# DAC_IO.net
KiCad netlist of a schematic drawn in Altium Designer
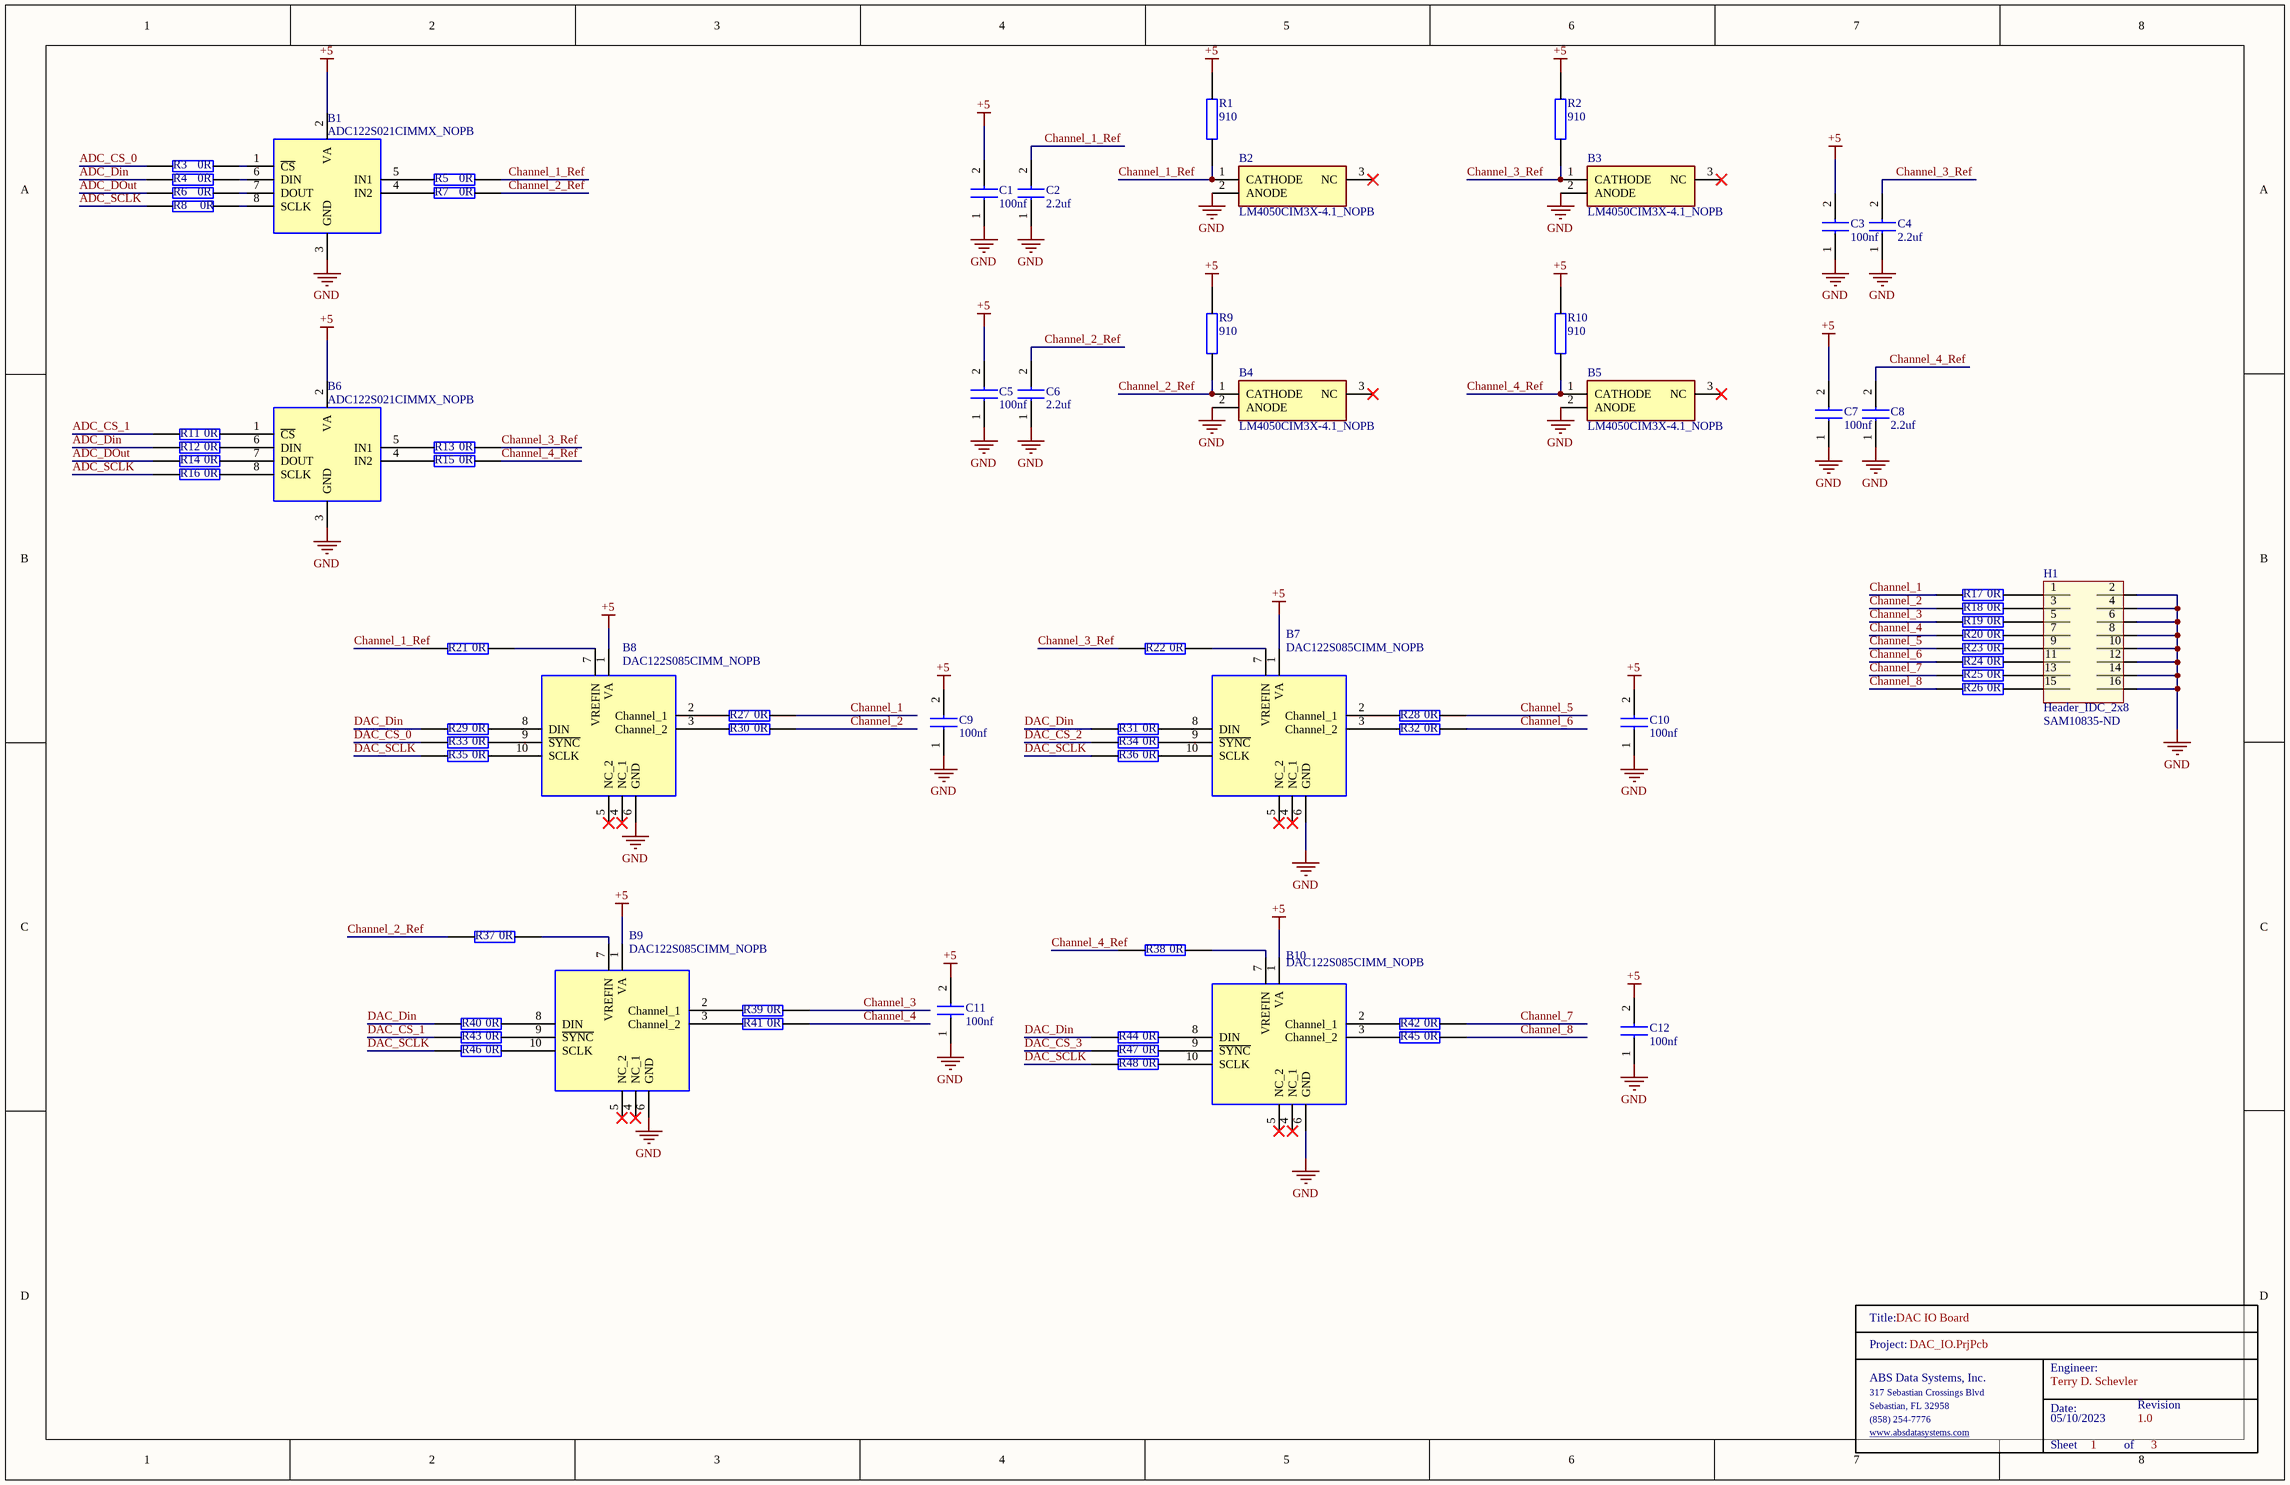
[diagram p0: DAC_IO.SchDoc]

(export (version "E")
  (design (tool "Eeschema 10.0.6"))
  (components
    (comp (ref "B1")
      (value "ADC122S021CIMMX_NOPB")
      (footprint "SOP65P490X110-8N")
      (description "2 Channel, 50 ksps to 200 ksps 12-Bit A/D Converter")
      (fields
        (field (name "MOUSER PART NUMBER") "926-A122S021CIMMXNPB")
        (field (name "MANUFACTURER_PART_NUMBER") "ADC122S021CIMMX/NOPB")
      )
      (libsource (lib "SemiConductors") (part "ADC122S021CIMMX_NOPB"))
    )
    (comp (ref "B2")
      (value "LM4050CIM3X-4.1_NOPB")
      (footprint "SOT95P237X95-3N")
      (description "50ppm/C Precision Micropower Shunt Voltage Reference")
      (fields
        (field (name "MOUSER PART NUMBER") "926-LM4050CIM3X41NPB")
        (field (name "MANUFACTURER_PART_NUMBER") "LM4050CIM3X-4.1/NOPB")
      )
      (libsource (lib "SemiConductors") (part "LM4050CIM3X-4.1_NOPB"))
    )
    (comp (ref "B3")
      (value "LM4050CIM3X-4.1_NOPB")
      (footprint "SOT95P237X95-3N")
      (description "50ppm/C Precision Micropower Shunt Voltage Reference")
      (fields
        (field (name "MOUSER PART NUMBER") "926-LM4050CIM3X41NPB")
        (field (name "MANUFACTURER_PART_NUMBER") "LM4050CIM3X-4.1/NOPB")
      )
      (libsource (lib "SemiConductors") (part "LM4050CIM3X-4.1_NOPB"))
    )
    (comp (ref "B4")
      (value "LM4050CIM3X-4.1_NOPB")
      (footprint "SOT95P237X95-3N")
      (description "50ppm/C Precision Micropower Shunt Voltage Reference")
      (fields
        (field (name "MOUSER PART NUMBER") "926-LM4050CIM3X41NPB")
        (field (name "MANUFACTURER_PART_NUMBER") "LM4050CIM3X-4.1/NOPB")
      )
      (libsource (lib "SemiConductors") (part "LM4050CIM3X-4.1_NOPB"))
    )
    (comp (ref "B5")
      (value "LM4050CIM3X-4.1_NOPB")
      (footprint "SOT95P237X95-3N")
      (description "50ppm/C Precision Micropower Shunt Voltage Reference")
      (fields
        (field (name "MOUSER PART NUMBER") "926-LM4050CIM3X41NPB")
        (field (name "MANUFACTURER_PART_NUMBER") "LM4050CIM3X-4.1/NOPB")
      )
      (libsource (lib "SemiConductors") (part "LM4050CIM3X-4.1_NOPB"))
    )
    (comp (ref "B6")
      (value "ADC122S021CIMMX_NOPB")
      (footprint "SOP65P490X110-8N")
      (description "2 Channel, 50 ksps to 200 ksps 12-Bit A/D Converter")
      (fields
        (field (name "MOUSER PART NUMBER") "926-A122S021CIMMXNPB")
        (field (name "MANUFACTURER_PART_NUMBER") "ADC122S021CIMMX/NOPB")
      )
      (libsource (lib "SemiConductors") (part "ADC122S021CIMMX_NOPB"))
    )
    (comp (ref "B7")
      (value "DAC122S085CIMM_NOPB")
      (footprint "SOP50P490X110-10N")
      (description "12-Bit Micro Power DUAL Digital-to-Analog Converter with Rail-to-Rail Output")
      (fields
        (field (name "MOUSER PART NUMBER") "926-DAC122S085CIMMNO")
        (field (name "MANUFACTURER_PART_NUMBER") "DAC122S085CIMM/NOPB")
      )
      (libsource (lib "SemiConductors") (part "DAC122S085CIMM_NOPB"))
    )
    (comp (ref "B8")
      (value "DAC122S085CIMM_NOPB")
      (footprint "SOP50P490X110-10N")
      (description "12-Bit Micro Power DUAL Digital-to-Analog Converter with Rail-to-Rail Output")
      (fields
        (field (name "MOUSER PART NUMBER") "926-DAC122S085CIMMNO")
        (field (name "MANUFACTURER_PART_NUMBER") "DAC122S085CIMM/NOPB")
      )
      (libsource (lib "SemiConductors") (part "DAC122S085CIMM_NOPB"))
    )
    (comp (ref "B9")
      (value "DAC122S085CIMM_NOPB")
      (footprint "SOP50P490X110-10N")
      (description "12-Bit Micro Power DUAL Digital-to-Analog Converter with Rail-to-Rail Output")
      (fields
        (field (name "MOUSER PART NUMBER") "926-DAC122S085CIMMNO")
        (field (name "MANUFACTURER_PART_NUMBER") "DAC122S085CIMM/NOPB")
      )
      (libsource (lib "SemiConductors") (part "DAC122S085CIMM_NOPB"))
    )
    (comp (ref "B10")
      (value "DAC122S085CIMM_NOPB")
      (footprint "SOP50P490X110-10N")
      (description "12-Bit Micro Power DUAL Digital-to-Analog Converter with Rail-to-Rail Output")
      (fields
        (field (name "MOUSER PART NUMBER") "926-DAC122S085CIMMNO")
        (field (name "MANUFACTURER_PART_NUMBER") "DAC122S085CIMM/NOPB")
      )
      (libsource (lib "SemiConductors") (part "DAC122S085CIMM_NOPB"))
    )
    (comp (ref "C1")
      (value "100nf")
      (footprint "0603")
      (description "Samsung Electro-Mechanics 0603 100nf")
      (libsource (lib "Capacitors") (part "CL10B104JB8NNNC"))
    )
    (comp (ref "C2")
      (value "2.2uf")
      (footprint "0603")
      (description "Samsung Electro-Mechanics 0603 2.2uf")
      (libsource (lib "Capacitors") (part "CL10B225KP8NNNC"))
    )
    (comp (ref "C3")
      (value "100nf")
      (footprint "0603")
      (description "Samsung Electro-Mechanics 0603 100nf")
      (libsource (lib "Capacitors") (part "CL10B104JB8NNNC"))
    )
    (comp (ref "C4")
      (value "2.2uf")
      (footprint "0603")
      (description "Samsung Electro-Mechanics 0603 2.2uf")
      (libsource (lib "Capacitors") (part "CL10B225KP8NNNC"))
    )
    (comp (ref "C5")
      (value "100nf")
      (footprint "0603")
      (description "Samsung Electro-Mechanics 0603 100nf")
      (libsource (lib "Capacitors") (part "CL10B104JB8NNNC"))
    )
    (comp (ref "C6")
      (value "2.2uf")
      (footprint "0603")
      (description "Samsung Electro-Mechanics 0603 2.2uf")
      (libsource (lib "Capacitors") (part "CL10B225KP8NNNC"))
    )
    (comp (ref "C7")
      (value "100nf")
      (footprint "0603")
      (description "Samsung Electro-Mechanics 0603 100nf")
      (libsource (lib "Capacitors") (part "CL10B104JB8NNNC"))
    )
    (comp (ref "C8")
      (value "2.2uf")
      (footprint "0603")
      (description "Samsung Electro-Mechanics 0603 2.2uf")
      (libsource (lib "Capacitors") (part "CL10B225KP8NNNC"))
    )
    (comp (ref "C9")
      (value "100nf")
      (footprint "0603")
      (description "Samsung Electro-Mechanics 0603 100nf")
      (libsource (lib "Capacitors") (part "CL10B104JB8NNNC"))
    )
    (comp (ref "C10")
      (value "100nf")
      (footprint "0603")
      (description "Samsung Electro-Mechanics 0603 100nf")
      (libsource (lib "Capacitors") (part "CL10B104JB8NNNC"))
    )
    (comp (ref "C11")
      (value "100nf")
      (footprint "0603")
      (description "Samsung Electro-Mechanics 0603 100nf")
      (libsource (lib "Capacitors") (part "CL10B104JB8NNNC"))
    )
    (comp (ref "C12")
      (value "100nf")
      (footprint "0603")
      (description "Samsung Electro-Mechanics 0603 100nf")
      (libsource (lib "Capacitors") (part "CL10B104JB8NNNC"))
    )
    (comp (ref "H1")
      (value "Header_IDC_2x8")
      (footprint "HEADER16")
      (description "16 Pin 2x8 Through Hold IDC Connector")
      (fields
        (field (name "MANUFACTURER") "Samtec")
        (field (name "MANUFACTURER PART NUMBER") "TST-108-01-G-D")
        (field (name "SUPPLIER PART NUMBER 1") "SAM10835-ND")
      )
      (libsource (lib "Misc") (part "Header_IDC_2x8"))
    )
    (comp (ref "R1")
      (value "910")
      (footprint "0603")
      (description "YAGEO 0603 910 ohm")
      (fields
        (field (name "MOUSER PART NUMBER") "603-RC0603JR-070RL")
        (field (name "MANUFACTURER_PART_NUMBER") "RC0603JR-070RL")
      )
      (libsource (lib "Resistors") (part "RT0603BRC07910RL"))
    )
    (comp (ref "R2")
      (value "910")
      (footprint "0603")
      (description "YAGEO 0603 910 ohm")
      (fields
        (field (name "MOUSER PART NUMBER") "603-RC0603JR-070RL")
        (field (name "MANUFACTURER_PART_NUMBER") "RC0603JR-070RL")
      )
      (libsource (lib "Resistors") (part "RT0603BRC07910RL"))
    )
    (comp (ref "R3")
      (value "0R")
      (footprint "0603")
      (description "YAGEO 0603 0 ohm")
      (fields
        (field (name "MOUSER PART NUMBER") "603-RC0603JR-070RL")
        (field (name "MANUFACTURER_PART_NUMBER") "RC0603JR-070RL")
      )
      (libsource (lib "Resistors") (part "RC0603JR-070RL"))
    )
    (comp (ref "R4")
      (value "0R")
      (footprint "0603")
      (description "YAGEO 0603 0 ohm")
      (fields
        (field (name "MOUSER PART NUMBER") "603-RC0603JR-070RL")
        (field (name "MANUFACTURER_PART_NUMBER") "RC0603JR-070RL")
      )
      (libsource (lib "Resistors") (part "RC0603JR-070RL"))
    )
    (comp (ref "R5")
      (value "0R")
      (footprint "0603")
      (description "YAGEO 0603 0 ohm")
      (fields
        (field (name "MOUSER PART NUMBER") "603-RC0603JR-070RL")
        (field (name "MANUFACTURER_PART_NUMBER") "RC0603JR-070RL")
      )
      (libsource (lib "Resistors") (part "RC0603JR-070RL"))
    )
    (comp (ref "R6")
      (value "0R")
      (footprint "0603")
      (description "YAGEO 0603 0 ohm")
      (fields
        (field (name "MOUSER PART NUMBER") "603-RC0603JR-070RL")
        (field (name "MANUFACTURER_PART_NUMBER") "RC0603JR-070RL")
      )
      (libsource (lib "Resistors") (part "RC0603JR-070RL"))
    )
    (comp (ref "R7")
      (value "0R")
      (footprint "0603")
      (description "YAGEO 0603 0 ohm")
      (fields
        (field (name "MOUSER PART NUMBER") "603-RC0603JR-070RL")
        (field (name "MANUFACTURER_PART_NUMBER") "RC0603JR-070RL")
      )
      (libsource (lib "Resistors") (part "RC0603JR-070RL"))
    )
    (comp (ref "R8")
      (value "0R")
      (footprint "0603")
      (description "YAGEO 0603 0 ohm")
      (fields
        (field (name "MOUSER PART NUMBER") "603-RC0603JR-070RL")
        (field (name "MANUFACTURER_PART_NUMBER") "RC0603JR-070RL")
      )
      (libsource (lib "Resistors") (part "RC0603JR-070RL"))
    )
    (comp (ref "R9")
      (value "910")
      (footprint "0603")
      (description "YAGEO 0603 910 ohm")
      (fields
        (field (name "MOUSER PART NUMBER") "603-RC0603JR-070RL")
        (field (name "MANUFACTURER_PART_NUMBER") "RC0603JR-070RL")
      )
      (libsource (lib "Resistors") (part "RT0603BRC07910RL"))
    )
    (comp (ref "R10")
      (value "910")
      (footprint "0603")
      (description "YAGEO 0603 910 ohm")
      (fields
        (field (name "MOUSER PART NUMBER") "603-RC0603JR-070RL")
        (field (name "MANUFACTURER_PART_NUMBER") "RC0603JR-070RL")
      )
      (libsource (lib "Resistors") (part "RT0603BRC07910RL"))
    )
    (comp (ref "R11")
      (value "0R")
      (footprint "0603")
      (description "YAGEO 0603 0 ohm")
      (fields
        (field (name "MOUSER PART NUMBER") "603-RC0603JR-070RL")
        (field (name "MANUFACTURER_PART_NUMBER") "RC0603JR-070RL")
      )
      (libsource (lib "Resistors") (part "RC0603JR-070RL"))
    )
    (comp (ref "R12")
      (value "0R")
      (footprint "0603")
      (description "YAGEO 0603 0 ohm")
      (fields
        (field (name "MOUSER PART NUMBER") "603-RC0603JR-070RL")
        (field (name "MANUFACTURER_PART_NUMBER") "RC0603JR-070RL")
      )
      (libsource (lib "Resistors") (part "RC0603JR-070RL"))
    )
    (comp (ref "R13")
      (value "0R")
      (footprint "0603")
      (description "YAGEO 0603 0 ohm")
      (fields
        (field (name "MOUSER PART NUMBER") "603-RC0603JR-070RL")
        (field (name "MANUFACTURER_PART_NUMBER") "RC0603JR-070RL")
      )
      (libsource (lib "Resistors") (part "RC0603JR-070RL"))
    )
    (comp (ref "R14")
      (value "0R")
      (footprint "0603")
      (description "YAGEO 0603 0 ohm")
      (fields
        (field (name "MOUSER PART NUMBER") "603-RC0603JR-070RL")
        (field (name "MANUFACTURER_PART_NUMBER") "RC0603JR-070RL")
      )
      (libsource (lib "Resistors") (part "RC0603JR-070RL"))
    )
    (comp (ref "R15")
      (value "0R")
      (footprint "0603")
      (description "YAGEO 0603 0 ohm")
      (fields
        (field (name "MOUSER PART NUMBER") "603-RC0603JR-070RL")
        (field (name "MANUFACTURER_PART_NUMBER") "RC0603JR-070RL")
      )
      (libsource (lib "Resistors") (part "RC0603JR-070RL"))
    )
    (comp (ref "R16")
      (value "0R")
      (footprint "0603")
      (description "YAGEO 0603 0 ohm")
      (fields
        (field (name "MOUSER PART NUMBER") "603-RC0603JR-070RL")
        (field (name "MANUFACTURER_PART_NUMBER") "RC0603JR-070RL")
      )
      (libsource (lib "Resistors") (part "RC0603JR-070RL"))
    )
    (comp (ref "R17")
      (value "0R")
      (footprint "0603")
      (description "YAGEO 0603 0 ohm")
      (fields
        (field (name "MOUSER PART NUMBER") "603-RC0603JR-070RL")
        (field (name "MANUFACTURER_PART_NUMBER") "RC0603JR-070RL")
      )
      (libsource (lib "Resistors") (part "RC0603JR-070RL"))
    )
    (comp (ref "R18")
      (value "0R")
      (footprint "0603")
      (description "YAGEO 0603 0 ohm")
      (fields
        (field (name "MOUSER PART NUMBER") "603-RC0603JR-070RL")
        (field (name "MANUFACTURER_PART_NUMBER") "RC0603JR-070RL")
      )
      (libsource (lib "Resistors") (part "RC0603JR-070RL"))
    )
    (comp (ref "R19")
      (value "0R")
      (footprint "0603")
      (description "YAGEO 0603 0 ohm")
      (fields
        (field (name "MOUSER PART NUMBER") "603-RC0603JR-070RL")
        (field (name "MANUFACTURER_PART_NUMBER") "RC0603JR-070RL")
      )
      (libsource (lib "Resistors") (part "RC0603JR-070RL"))
    )
    (comp (ref "R20")
      (value "0R")
      (footprint "0603")
      (description "YAGEO 0603 0 ohm")
      (fields
        (field (name "MOUSER PART NUMBER") "603-RC0603JR-070RL")
        (field (name "MANUFACTURER_PART_NUMBER") "RC0603JR-070RL")
      )
      (libsource (lib "Resistors") (part "RC0603JR-070RL"))
    )
    (comp (ref "R21")
      (value "0R")
      (footprint "0603")
      (description "YAGEO 0603 0 ohm")
      (fields
        (field (name "MOUSER PART NUMBER") "603-RC0603JR-070RL")
        (field (name "MANUFACTURER_PART_NUMBER") "RC0603JR-070RL")
      )
      (libsource (lib "Resistors") (part "RC0603JR-070RL"))
    )
    (comp (ref "R22")
      (value "0R")
      (footprint "0603")
      (description "YAGEO 0603 0 ohm")
      (fields
        (field (name "MOUSER PART NUMBER") "603-RC0603JR-070RL")
        (field (name "MANUFACTURER_PART_NUMBER") "RC0603JR-070RL")
      )
      (libsource (lib "Resistors") (part "RC0603JR-070RL"))
    )
    (comp (ref "R23")
      (value "0R")
      (footprint "0603")
      (description "YAGEO 0603 0 ohm")
      (fields
        (field (name "MOUSER PART NUMBER") "603-RC0603JR-070RL")
        (field (name "MANUFACTURER_PART_NUMBER") "RC0603JR-070RL")
      )
      (libsource (lib "Resistors") (part "RC0603JR-070RL"))
    )
    (comp (ref "R24")
      (value "0R")
      (footprint "0603")
      (description "YAGEO 0603 0 ohm")
      (fields
        (field (name "MOUSER PART NUMBER") "603-RC0603JR-070RL")
        (field (name "MANUFACTURER_PART_NUMBER") "RC0603JR-070RL")
      )
      (libsource (lib "Resistors") (part "RC0603JR-070RL"))
    )
    (comp (ref "R25")
      (value "0R")
      (footprint "0603")
      (description "YAGEO 0603 0 ohm")
      (fields
        (field (name "MOUSER PART NUMBER") "603-RC0603JR-070RL")
        (field (name "MANUFACTURER_PART_NUMBER") "RC0603JR-070RL")
      )
      (libsource (lib "Resistors") (part "RC0603JR-070RL"))
    )
    (comp (ref "R26")
      (value "0R")
      (footprint "0603")
      (description "YAGEO 0603 0 ohm")
      (fields
        (field (name "MOUSER PART NUMBER") "603-RC0603JR-070RL")
        (field (name "MANUFACTURER_PART_NUMBER") "RC0603JR-070RL")
      )
      (libsource (lib "Resistors") (part "RC0603JR-070RL"))
    )
    (comp (ref "R27")
      (value "0R")
      (footprint "0603")
      (description "YAGEO 0603 0 ohm")
      (fields
        (field (name "MOUSER PART NUMBER") "603-RC0603JR-070RL")
        (field (name "MANUFACTURER_PART_NUMBER") "RC0603JR-070RL")
      )
      (libsource (lib "Resistors") (part "RC0603JR-070RL"))
    )
    (comp (ref "R28")
      (value "0R")
      (footprint "0603")
      (description "YAGEO 0603 0 ohm")
      (fields
        (field (name "MOUSER PART NUMBER") "603-RC0603JR-070RL")
        (field (name "MANUFACTURER_PART_NUMBER") "RC0603JR-070RL")
      )
      (libsource (lib "Resistors") (part "RC0603JR-070RL"))
    )
    (comp (ref "R29")
      (value "0R")
      (footprint "0603")
      (description "YAGEO 0603 0 ohm")
      (fields
        (field (name "MOUSER PART NUMBER") "603-RC0603JR-070RL")
        (field (name "MANUFACTURER_PART_NUMBER") "RC0603JR-070RL")
      )
      (libsource (lib "Resistors") (part "RC0603JR-070RL"))
    )
    (comp (ref "R30")
      (value "0R")
      (footprint "0603")
      (description "YAGEO 0603 0 ohm")
      (fields
        (field (name "MOUSER PART NUMBER") "603-RC0603JR-070RL")
        (field (name "MANUFACTURER_PART_NUMBER") "RC0603JR-070RL")
      )
      (libsource (lib "Resistors") (part "RC0603JR-070RL"))
    )
    (comp (ref "R31")
      (value "0R")
      (footprint "0603")
      (description "YAGEO 0603 0 ohm")
      (fields
        (field (name "MOUSER PART NUMBER") "603-RC0603JR-070RL")
        (field (name "MANUFACTURER_PART_NUMBER") "RC0603JR-070RL")
      )
      (libsource (lib "Resistors") (part "RC0603JR-070RL"))
    )
    (comp (ref "R32")
      (value "0R")
      (footprint "0603")
      (description "YAGEO 0603 0 ohm")
      (fields
        (field (name "MOUSER PART NUMBER") "603-RC0603JR-070RL")
        (field (name "MANUFACTURER_PART_NUMBER") "RC0603JR-070RL")
      )
      (libsource (lib "Resistors") (part "RC0603JR-070RL"))
    )
    (comp (ref "R33")
      (value "0R")
      (footprint "0603")
      (description "YAGEO 0603 0 ohm")
      (fields
        (field (name "MOUSER PART NUMBER") "603-RC0603JR-070RL")
        (field (name "MANUFACTURER_PART_NUMBER") "RC0603JR-070RL")
      )
      (libsource (lib "Resistors") (part "RC0603JR-070RL"))
    )
    (comp (ref "R34")
      (value "0R")
      (footprint "0603")
      (description "YAGEO 0603 0 ohm")
      (fields
        (field (name "MOUSER PART NUMBER") "603-RC0603JR-070RL")
        (field (name "MANUFACTURER_PART_NUMBER") "RC0603JR-070RL")
      )
      (libsource (lib "Resistors") (part "RC0603JR-070RL"))
    )
    (comp (ref "R35")
      (value "0R")
      (footprint "0603")
      (description "YAGEO 0603 0 ohm")
      (fields
        (field (name "MOUSER PART NUMBER") "603-RC0603JR-070RL")
        (field (name "MANUFACTURER_PART_NUMBER") "RC0603JR-070RL")
      )
      (libsource (lib "Resistors") (part "RC0603JR-070RL"))
    )
    (comp (ref "R36")
      (value "0R")
      (footprint "0603")
      (description "YAGEO 0603 0 ohm")
      (fields
        (field (name "MOUSER PART NUMBER") "603-RC0603JR-070RL")
        (field (name "MANUFACTURER_PART_NUMBER") "RC0603JR-070RL")
      )
      (libsource (lib "Resistors") (part "RC0603JR-070RL"))
    )
    (comp (ref "R37")
      (value "0R")
      (footprint "0603")
      (description "YAGEO 0603 0 ohm")
      (fields
        (field (name "MOUSER PART NUMBER") "603-RC0603JR-070RL")
        (field (name "MANUFACTURER_PART_NUMBER") "RC0603JR-070RL")
      )
      (libsource (lib "Resistors") (part "RC0603JR-070RL"))
    )
    (comp (ref "R38")
      (value "0R")
      (footprint "0603")
      (description "YAGEO 0603 0 ohm")
      (fields
        (field (name "MOUSER PART NUMBER") "603-RC0603JR-070RL")
        (field (name "MANUFACTURER_PART_NUMBER") "RC0603JR-070RL")
      )
      (libsource (lib "Resistors") (part "RC0603JR-070RL"))
    )
    (comp (ref "R39")
      (value "0R")
      (footprint "0603")
      (description "YAGEO 0603 0 ohm")
      (fields
        (field (name "MOUSER PART NUMBER") "603-RC0603JR-070RL")
        (field (name "MANUFACTURER_PART_NUMBER") "RC0603JR-070RL")
      )
      (libsource (lib "Resistors") (part "RC0603JR-070RL"))
    )
    (comp (ref "R40")
      (value "0R")
      (footprint "0603")
      (description "YAGEO 0603 0 ohm")
      (fields
        (field (name "MOUSER PART NUMBER") "603-RC0603JR-070RL")
        (field (name "MANUFACTURER_PART_NUMBER") "RC0603JR-070RL")
      )
      (libsource (lib "Resistors") (part "RC0603JR-070RL"))
    )
    (comp (ref "R41")
      (value "0R")
      (footprint "0603")
      (description "YAGEO 0603 0 ohm")
      (fields
        (field (name "MOUSER PART NUMBER") "603-RC0603JR-070RL")
        (field (name "MANUFACTURER_PART_NUMBER") "RC0603JR-070RL")
      )
      (libsource (lib "Resistors") (part "RC0603JR-070RL"))
    )
    (comp (ref "R42")
      (value "0R")
      (footprint "0603")
      (description "YAGEO 0603 0 ohm")
      (fields
        (field (name "MOUSER PART NUMBER") "603-RC0603JR-070RL")
        (field (name "MANUFACTURER_PART_NUMBER") "RC0603JR-070RL")
      )
      (libsource (lib "Resistors") (part "RC0603JR-070RL"))
    )
    (comp (ref "R43")
      (value "0R")
      (footprint "0603")
      (description "YAGEO 0603 0 ohm")
      (fields
        (field (name "MOUSER PART NUMBER") "603-RC0603JR-070RL")
        (field (name "MANUFACTURER_PART_NUMBER") "RC0603JR-070RL")
      )
      (libsource (lib "Resistors") (part "RC0603JR-070RL"))
    )
    (comp (ref "R44")
      (value "0R")
      (footprint "0603")
      (description "YAGEO 0603 0 ohm")
      (fields
        (field (name "MOUSER PART NUMBER") "603-RC0603JR-070RL")
        (field (name "MANUFACTURER_PART_NUMBER") "RC0603JR-070RL")
      )
      (libsource (lib "Resistors") (part "RC0603JR-070RL"))
    )
    (comp (ref "R45")
      (value "0R")
      (footprint "0603")
      (description "YAGEO 0603 0 ohm")
      (fields
        (field (name "MOUSER PART NUMBER") "603-RC0603JR-070RL")
        (field (name "MANUFACTURER_PART_NUMBER") "RC0603JR-070RL")
      )
      (libsource (lib "Resistors") (part "RC0603JR-070RL"))
    )
    (comp (ref "R46")
      (value "0R")
      (footprint "0603")
      (description "YAGEO 0603 0 ohm")
      (fields
        (field (name "MOUSER PART NUMBER") "603-RC0603JR-070RL")
        (field (name "MANUFACTURER_PART_NUMBER") "RC0603JR-070RL")
      )
      (libsource (lib "Resistors") (part "RC0603JR-070RL"))
    )
    (comp (ref "R47")
      (value "0R")
      (footprint "0603")
      (description "YAGEO 0603 0 ohm")
      (fields
        (field (name "MOUSER PART NUMBER") "603-RC0603JR-070RL")
        (field (name "MANUFACTURER_PART_NUMBER") "RC0603JR-070RL")
      )
      (libsource (lib "Resistors") (part "RC0603JR-070RL"))
    )
    (comp (ref "R48")
      (value "0R")
      (footprint "0603")
      (description "YAGEO 0603 0 ohm")
      (fields
        (field (name "MOUSER PART NUMBER") "603-RC0603JR-070RL")
        (field (name "MANUFACTURER_PART_NUMBER") "RC0603JR-070RL")
      )
      (libsource (lib "Resistors") (part "RC0603JR-070RL"))
    )
    (comp (ref "TitleBlock_1") (value "TitleBlock") (libsource (lib "Misc") (part "TitleBlock")))
  )
  (nets
    (net (code "1") (name "+5") (class "Default")
      (node (ref "B1") (pin "2") (pinfunction "VA_2") (pintype "passive"))
      (node (ref "B10") (pin "1") (pinfunction "VA_1") (pintype "passive"))
      (node (ref "B6") (pin "2") (pinfunction "VA_2") (pintype "passive"))
      (node (ref "B7") (pin "1") (pinfunction "VA_1") (pintype "passive"))
      (node (ref "B8") (pin "1") (pinfunction "VA_1") (pintype "passive"))
      (node (ref "B9") (pin "1") (pinfunction "VA_1") (pintype "passive"))
      (node (ref "C1") (pin "2") (pinfunction "2_2") (pintype "passive"))
      (node (ref "C10") (pin "2") (pinfunction "2_2") (pintype "passive"))
      (node (ref "C11") (pin "2") (pinfunction "2_2") (pintype "passive"))
      (node (ref "C12") (pin "2") (pinfunction "2_2") (pintype "passive"))
      (node (ref "C3") (pin "2") (pinfunction "2_2") (pintype "passive"))
      (node (ref "C5") (pin "2") (pinfunction "2_2") (pintype "passive"))
      (node (ref "C7") (pin "2") (pinfunction "2_2") (pintype "passive"))
      (node (ref "C9") (pin "2") (pinfunction "2_2") (pintype "passive"))
      (node (ref "R1") (pin "1") (pinfunction "1_1") (pintype "passive"))
      (node (ref "R10") (pin "1") (pinfunction "1_1") (pintype "passive"))
      (node (ref "R2") (pin "1") (pinfunction "1_1") (pintype "passive"))
      (node (ref "R9") (pin "1") (pinfunction "1_1") (pintype "passive"))
    )
    (net (code "2") (name "/ADC_CS_0") (class "Default")
      (node (ref "R3") (pin "1") (pinfunction "1_1") (pintype "passive"))
    )
    (net (code "3") (name "/ADC_CS_1") (class "Default")
      (node (ref "R11") (pin "1") (pinfunction "1_1") (pintype "passive"))
    )
    (net (code "4") (name "/ADC_DOut") (class "Default")
      (node (ref "R14") (pin "1") (pinfunction "1_1") (pintype "passive"))
      (node (ref "R6") (pin "1") (pinfunction "1_1") (pintype "passive"))
    )
    (net (code "5") (name "/ADC_Din") (class "Default")
      (node (ref "R12") (pin "1") (pinfunction "1_1") (pintype "passive"))
      (node (ref "R4") (pin "1") (pinfunction "1_1") (pintype "passive"))
    )
    (net (code "6") (name "/ADC_SCLK") (class "Default")
      (node (ref "R16") (pin "1") (pinfunction "1_1") (pintype "passive"))
      (node (ref "R8") (pin "1") (pinfunction "1_1") (pintype "passive"))
    )
    (net (code "7") (name "/Channel_1") (class "Default")
      (node (ref "R17") (pin "1") (pinfunction "1_1") (pintype "passive"))
      (node (ref "R27") (pin "2") (pinfunction "2_2") (pintype "passive"))
    )
    (net (code "8") (name "/Channel_1_Ref") (class "Default")
      (node (ref "B2") (pin "1") (pinfunction "CATHODE_1") (pintype "passive"))
      (node (ref "C2") (pin "2") (pinfunction "2_2") (pintype "passive"))
      (node (ref "R1") (pin "2") (pinfunction "2_2") (pintype "passive"))
      (node (ref "R21") (pin "1") (pinfunction "1_1") (pintype "passive"))
      (node (ref "R5") (pin "2") (pinfunction "2_2") (pintype "passive"))
    )
    (net (code "9") (name "/Channel_2") (class "Default")
      (node (ref "R18") (pin "1") (pinfunction "1_1") (pintype "passive"))
      (node (ref "R30") (pin "2") (pinfunction "2_2") (pintype "passive"))
    )
    (net (code "10") (name "/Channel_2_Ref") (class "Default")
      (node (ref "B4") (pin "1") (pinfunction "CATHODE_1") (pintype "passive"))
      (node (ref "C6") (pin "2") (pinfunction "2_2") (pintype "passive"))
      (node (ref "R37") (pin "1") (pinfunction "1_1") (pintype "passive"))
      (node (ref "R7") (pin "2") (pinfunction "2_2") (pintype "passive"))
      (node (ref "R9") (pin "2") (pinfunction "2_2") (pintype "passive"))
    )
    (net (code "11") (name "/Channel_3") (class "Default")
      (node (ref "R19") (pin "1") (pinfunction "1_1") (pintype "passive"))
      (node (ref "R39") (pin "2") (pinfunction "2_2") (pintype "passive"))
    )
    (net (code "12") (name "/Channel_3_Ref") (class "Default")
      (node (ref "B3") (pin "1") (pinfunction "CATHODE_1") (pintype "passive"))
      (node (ref "C4") (pin "2") (pinfunction "2_2") (pintype "passive"))
      (node (ref "R13") (pin "2") (pinfunction "2_2") (pintype "passive"))
      (node (ref "R2") (pin "2") (pinfunction "2_2") (pintype "passive"))
      (node (ref "R22") (pin "1") (pinfunction "1_1") (pintype "passive"))
    )
    (net (code "13") (name "/Channel_4") (class "Default")
      (node (ref "R20") (pin "1") (pinfunction "1_1") (pintype "passive"))
      (node (ref "R41") (pin "2") (pinfunction "2_2") (pintype "passive"))
    )
    (net (code "14") (name "/Channel_4_Ref") (class "Default")
      (node (ref "B5") (pin "1") (pinfunction "CATHODE_1") (pintype "passive"))
      (node (ref "C8") (pin "2") (pinfunction "2_2") (pintype "passive"))
      (node (ref "R10") (pin "2") (pinfunction "2_2") (pintype "passive"))
      (node (ref "R15") (pin "2") (pinfunction "2_2") (pintype "passive"))
      (node (ref "R38") (pin "1") (pinfunction "1_1") (pintype "passive"))
    )
    (net (code "15") (name "/Channel_5") (class "Default")
      (node (ref "R23") (pin "1") (pinfunction "1_1") (pintype "passive"))
      (node (ref "R28") (pin "2") (pinfunction "2_2") (pintype "passive"))
    )
    (net (code "16") (name "/Channel_6") (class "Default")
      (node (ref "R24") (pin "1") (pinfunction "1_1") (pintype "passive"))
      (node (ref "R32") (pin "2") (pinfunction "2_2") (pintype "passive"))
    )
    (net (code "17") (name "/Channel_7") (class "Default")
      (node (ref "R25") (pin "1") (pinfunction "1_1") (pintype "passive"))
      (node (ref "R42") (pin "2") (pinfunction "2_2") (pintype "passive"))
    )
    (net (code "18") (name "/Channel_8") (class "Default")
      (node (ref "R26") (pin "1") (pinfunction "1_1") (pintype "passive"))
      (node (ref "R45") (pin "2") (pinfunction "2_2") (pintype "passive"))
    )
    (net (code "19") (name "/DAC_CS_0") (class "Default")
      (node (ref "R33") (pin "1") (pinfunction "1_1") (pintype "passive"))
    )
    (net (code "20") (name "/DAC_CS_1") (class "Default")
      (node (ref "R43") (pin "1") (pinfunction "1_1") (pintype "passive"))
    )
    (net (code "21") (name "/DAC_CS_2") (class "Default")
      (node (ref "R34") (pin "1") (pinfunction "1_1") (pintype "passive"))
    )
    (net (code "22") (name "/DAC_CS_3") (class "Default")
      (node (ref "R47") (pin "1") (pinfunction "1_1") (pintype "passive"))
    )
    (net (code "23") (name "/DAC_Din") (class "Default")
      (node (ref "R29") (pin "1") (pinfunction "1_1") (pintype "passive"))
      (node (ref "R31") (pin "1") (pinfunction "1_1") (pintype "passive"))
      (node (ref "R40") (pin "1") (pinfunction "1_1") (pintype "passive"))
      (node (ref "R44") (pin "1") (pinfunction "1_1") (pintype "passive"))
    )
    (net (code "24") (name "/DAC_SCLK") (class "Default")
      (node (ref "R35") (pin "1") (pinfunction "1_1") (pintype "passive"))
      (node (ref "R36") (pin "1") (pinfunction "1_1") (pintype "passive"))
      (node (ref "R46") (pin "1") (pinfunction "1_1") (pintype "passive"))
      (node (ref "R48") (pin "1") (pinfunction "1_1") (pintype "passive"))
    )
    (net (code "25") (name "GND") (class "Default")
      (node (ref "B1") (pin "3") (pinfunction "GND_3") (pintype "passive"))
      (node (ref "B10") (pin "6") (pinfunction "GND_6") (pintype "passive"))
      (node (ref "B2") (pin "2") (pinfunction "ANODE_2") (pintype "passive"))
      (node (ref "B3") (pin "2") (pinfunction "ANODE_2") (pintype "passive"))
      (node (ref "B4") (pin "2") (pinfunction "ANODE_2") (pintype "passive"))
      (node (ref "B5") (pin "2") (pinfunction "ANODE_2") (pintype "passive"))
      (node (ref "B6") (pin "3") (pinfunction "GND_3") (pintype "passive"))
      (node (ref "B7") (pin "6") (pinfunction "GND_6") (pintype "passive"))
      (node (ref "B8") (pin "6") (pinfunction "GND_6") (pintype "passive"))
      (node (ref "B9") (pin "6") (pinfunction "GND_6") (pintype "passive"))
      (node (ref "C1") (pin "1") (pinfunction "1_1") (pintype "passive"))
      (node (ref "C10") (pin "1") (pinfunction "1_1") (pintype "passive"))
      (node (ref "C11") (pin "1") (pinfunction "1_1") (pintype "passive"))
      (node (ref "C12") (pin "1") (pinfunction "1_1") (pintype "passive"))
      (node (ref "C2") (pin "1") (pinfunction "1_1") (pintype "passive"))
      (node (ref "C3") (pin "1") (pinfunction "1_1") (pintype "passive"))
      (node (ref "C4") (pin "1") (pinfunction "1_1") (pintype "passive"))
      (node (ref "C5") (pin "1") (pinfunction "1_1") (pintype "passive"))
      (node (ref "C6") (pin "1") (pinfunction "1_1") (pintype "passive"))
      (node (ref "C7") (pin "1") (pinfunction "1_1") (pintype "passive"))
      (node (ref "C8") (pin "1") (pinfunction "1_1") (pintype "passive"))
      (node (ref "C9") (pin "1") (pinfunction "1_1") (pintype "passive"))
      (node (ref "H1") (pin "10") (pinfunction "10_10") (pintype "passive"))
      (node (ref "H1") (pin "12") (pinfunction "12_12") (pintype "passive"))
      (node (ref "H1") (pin "14") (pinfunction "14_14") (pintype "passive"))
      (node (ref "H1") (pin "16") (pinfunction "16_16") (pintype "passive"))
      (node (ref "H1") (pin "2") (pinfunction "2_2") (pintype "passive"))
      (node (ref "H1") (pin "4") (pinfunction "4_4") (pintype "passive"))
      (node (ref "H1") (pin "6") (pinfunction "6_6") (pintype "passive"))
      (node (ref "H1") (pin "8") (pinfunction "8_8") (pintype "passive"))
    )
    (net (code "26") (name "Net-(B1-DIN)") (class "Default")
      (node (ref "B1") (pin "6") (pinfunction "DIN_6") (pintype "passive"))
      (node (ref "R4") (pin "2") (pinfunction "2_2") (pintype "passive"))
    )
    (net (code "27") (name "Net-(B1-DOUT)") (class "Default")
      (node (ref "B1") (pin "7") (pinfunction "DOUT_7") (pintype "passive"))
      (node (ref "R6") (pin "2") (pinfunction "2_2") (pintype "passive"))
    )
    (net (code "28") (name "Net-(B1-IN1)") (class "Default")
      (node (ref "B1") (pin "5") (pinfunction "IN1_5") (pintype "passive"))
      (node (ref "R5") (pin "1") (pinfunction "1_1") (pintype "passive"))
    )
    (net (code "29") (name "Net-(B1-IN2)") (class "Default")
      (node (ref "B1") (pin "4") (pinfunction "IN2_4") (pintype "passive"))
      (node (ref "R7") (pin "1") (pinfunction "1_1") (pintype "passive"))
    )
    (net (code "30") (name "Net-(B1-SCLK)") (class "Default")
      (node (ref "B1") (pin "8") (pinfunction "SCLK_8") (pintype "passive"))
      (node (ref "R8") (pin "2") (pinfunction "2_2") (pintype "passive"))
    )
    (net (code "31") (name "Net-(B1-~{CS})") (class "Default")
      (node (ref "B1") (pin "1") (pinfunction "~{CS}_1") (pintype "passive"))
      (node (ref "R3") (pin "2") (pinfunction "2_2") (pintype "passive"))
    )
    (net (code "32") (name "Net-(B6-DIN)") (class "Default")
      (node (ref "B6") (pin "6") (pinfunction "DIN_6") (pintype "passive"))
      (node (ref "R12") (pin "2") (pinfunction "2_2") (pintype "passive"))
    )
    (net (code "33") (name "Net-(B6-DOUT)") (class "Default")
      (node (ref "B6") (pin "7") (pinfunction "DOUT_7") (pintype "passive"))
      (node (ref "R14") (pin "2") (pinfunction "2_2") (pintype "passive"))
    )
    (net (code "34") (name "Net-(B6-IN1)") (class "Default")
      (node (ref "B6") (pin "5") (pinfunction "IN1_5") (pintype "passive"))
      (node (ref "R13") (pin "1") (pinfunction "1_1") (pintype "passive"))
    )
    (net (code "35") (name "Net-(B6-IN2)") (class "Default")
      (node (ref "B6") (pin "4") (pinfunction "IN2_4") (pintype "passive"))
      (node (ref "R15") (pin "1") (pinfunction "1_1") (pintype "passive"))
    )
    (net (code "36") (name "Net-(B6-SCLK)") (class "Default")
      (node (ref "B6") (pin "8") (pinfunction "SCLK_8") (pintype "passive"))
      (node (ref "R16") (pin "2") (pinfunction "2_2") (pintype "passive"))
    )
    (net (code "37") (name "Net-(B6-~{CS})") (class "Default")
      (node (ref "B6") (pin "1") (pinfunction "~{CS}_1") (pintype "passive"))
      (node (ref "R11") (pin "2") (pinfunction "2_2") (pintype "passive"))
    )
    (net (code "38") (name "Net-(B7-Channel_1)") (class "Default")
      (node (ref "B7") (pin "2") (pinfunction "Channel_1_2") (pintype "passive"))
      (node (ref "R28") (pin "1") (pinfunction "1_1") (pintype "passive"))
    )
    (net (code "39") (name "Net-(B7-Channel_2)") (class "Default")
      (node (ref "B7") (pin "3") (pinfunction "Channel_2_3") (pintype "passive"))
      (node (ref "R32") (pin "1") (pinfunction "1_1") (pintype "passive"))
    )
    (net (code "40") (name "Net-(B7-DIN)") (class "Default")
      (node (ref "B7") (pin "8") (pinfunction "DIN_8") (pintype "passive"))
      (node (ref "R31") (pin "2") (pinfunction "2_2") (pintype "passive"))
    )
    (net (code "41") (name "Net-(B7-SCLK)") (class "Default")
      (node (ref "B7") (pin "10") (pinfunction "SCLK_10") (pintype "passive"))
      (node (ref "R36") (pin "2") (pinfunction "2_2") (pintype "passive"))
    )
    (net (code "42") (name "Net-(B7-VREFIN)") (class "Default")
      (node (ref "B7") (pin "7") (pinfunction "VREFIN_7") (pintype "passive"))
      (node (ref "R22") (pin "2") (pinfunction "2_2") (pintype "passive"))
    )
    (net (code "43") (name "Net-(B7-~{SYNC})") (class "Default")
      (node (ref "B7") (pin "9") (pinfunction "~{SYNC}_9") (pintype "passive"))
      (node (ref "R34") (pin "2") (pinfunction "2_2") (pintype "passive"))
    )
    (net (code "44") (name "Net-(B8-Channel_1)") (class "Default")
      (node (ref "B8") (pin "2") (pinfunction "Channel_1_2") (pintype "passive"))
      (node (ref "R27") (pin "1") (pinfunction "1_1") (pintype "passive"))
    )
    (net (code "45") (name "Net-(B8-Channel_2)") (class "Default")
      (node (ref "B8") (pin "3") (pinfunction "Channel_2_3") (pintype "passive"))
      (node (ref "R30") (pin "1") (pinfunction "1_1") (pintype "passive"))
    )
    (net (code "46") (name "Net-(B8-DIN)") (class "Default")
      (node (ref "B8") (pin "8") (pinfunction "DIN_8") (pintype "passive"))
      (node (ref "R29") (pin "2") (pinfunction "2_2") (pintype "passive"))
    )
    (net (code "47") (name "Net-(B8-SCLK)") (class "Default")
      (node (ref "B8") (pin "10") (pinfunction "SCLK_10") (pintype "passive"))
      (node (ref "R35") (pin "2") (pinfunction "2_2") (pintype "passive"))
    )
    (net (code "48") (name "Net-(B8-VREFIN)") (class "Default")
      (node (ref "B8") (pin "7") (pinfunction "VREFIN_7") (pintype "passive"))
      (node (ref "R21") (pin "2") (pinfunction "2_2") (pintype "passive"))
    )
    (net (code "49") (name "Net-(B8-~{SYNC})") (class "Default")
      (node (ref "B8") (pin "9") (pinfunction "~{SYNC}_9") (pintype "passive"))
      (node (ref "R33") (pin "2") (pinfunction "2_2") (pintype "passive"))
    )
    (net (code "50") (name "Net-(B9-Channel_1)") (class "Default")
      (node (ref "B9") (pin "2") (pinfunction "Channel_1_2") (pintype "passive"))
      (node (ref "R39") (pin "1") (pinfunction "1_1") (pintype "passive"))
    )
    (net (code "51") (name "Net-(B9-Channel_2)") (class "Default")
      (node (ref "B9") (pin "3") (pinfunction "Channel_2_3") (pintype "passive"))
      (node (ref "R41") (pin "1") (pinfunction "1_1") (pintype "passive"))
    )
    (net (code "52") (name "Net-(B9-DIN)") (class "Default")
      (node (ref "B9") (pin "8") (pinfunction "DIN_8") (pintype "passive"))
      (node (ref "R40") (pin "2") (pinfunction "2_2") (pintype "passive"))
    )
    (net (code "53") (name "Net-(B9-SCLK)") (class "Default")
      (node (ref "B9") (pin "10") (pinfunction "SCLK_10") (pintype "passive"))
      (node (ref "R46") (pin "2") (pinfunction "2_2") (pintype "passive"))
    )
    (net (code "54") (name "Net-(B9-VREFIN)") (class "Default")
      (node (ref "B9") (pin "7") (pinfunction "VREFIN_7") (pintype "passive"))
      (node (ref "R37") (pin "2") (pinfunction "2_2") (pintype "passive"))
    )
    (net (code "55") (name "Net-(B9-~{SYNC})") (class "Default")
      (node (ref "B9") (pin "9") (pinfunction "~{SYNC}_9") (pintype "passive"))
      (node (ref "R43") (pin "2") (pinfunction "2_2") (pintype "passive"))
    )
    (net (code "56") (name "Net-(B10-Channel_1)") (class "Default")
      (node (ref "B10") (pin "2") (pinfunction "Channel_1_2") (pintype "passive"))
      (node (ref "R42") (pin "1") (pinfunction "1_1") (pintype "passive"))
    )
    (net (code "57") (name "Net-(B10-Channel_2)") (class "Default")
      (node (ref "B10") (pin "3") (pinfunction "Channel_2_3") (pintype "passive"))
      (node (ref "R45") (pin "1") (pinfunction "1_1") (pintype "passive"))
    )
    (net (code "58") (name "Net-(B10-DIN)") (class "Default")
      (node (ref "B10") (pin "8") (pinfunction "DIN_8") (pintype "passive"))
      (node (ref "R44") (pin "2") (pinfunction "2_2") (pintype "passive"))
    )
    (net (code "59") (name "Net-(B10-SCLK)") (class "Default")
      (node (ref "B10") (pin "10") (pinfunction "SCLK_10") (pintype "passive"))
      (node (ref "R48") (pin "2") (pinfunction "2_2") (pintype "passive"))
    )
    (net (code "60") (name "Net-(B10-VREFIN)") (class "Default")
      (node (ref "B10") (pin "7") (pinfunction "VREFIN_7") (pintype "passive"))
      (node (ref "R38") (pin "2") (pinfunction "2_2") (pintype "passive"))
    )
    (net (code "61") (name "Net-(B10-~{SYNC})") (class "Default")
      (node (ref "B10") (pin "9") (pinfunction "~{SYNC}_9") (pintype "passive"))
      (node (ref "R47") (pin "2") (pinfunction "2_2") (pintype "passive"))
    )
    (net (code "62") (name "Net-(H1-Pad1)") (class "Default")
      (node (ref "H1") (pin "1") (pinfunction "1_1") (pintype "passive"))
      (node (ref "R17") (pin "2") (pinfunction "2_2") (pintype "passive"))
    )
    (net (code "63") (name "Net-(H1-Pad3)") (class "Default")
      (node (ref "H1") (pin "3") (pinfunction "3_3") (pintype "passive"))
      (node (ref "R18") (pin "2") (pinfunction "2_2") (pintype "passive"))
    )
    (net (code "64") (name "Net-(H1-Pad5)") (class "Default")
      (node (ref "H1") (pin "5") (pinfunction "5_5") (pintype "passive"))
      (node (ref "R19") (pin "2") (pinfunction "2_2") (pintype "passive"))
    )
    (net (code "65") (name "Net-(H1-Pad7)") (class "Default")
      (node (ref "H1") (pin "7") (pinfunction "7_7") (pintype "passive"))
      (node (ref "R20") (pin "2") (pinfunction "2_2") (pintype "passive"))
    )
    (net (code "66") (name "Net-(H1-Pad9)") (class "Default")
      (node (ref "H1") (pin "9") (pinfunction "9_9") (pintype "passive"))
      (node (ref "R23") (pin "2") (pinfunction "2_2") (pintype "passive"))
    )
    (net (code "67") (name "Net-(H1-Pad11)") (class "Default")
      (node (ref "H1") (pin "11") (pinfunction "11_11") (pintype "passive"))
      (node (ref "R24") (pin "2") (pinfunction "2_2") (pintype "passive"))
    )
    (net (code "68") (name "Net-(H1-Pad13)") (class "Default")
      (node (ref "H1") (pin "13") (pinfunction "13_13") (pintype "passive"))
      (node (ref "R25") (pin "2") (pinfunction "2_2") (pintype "passive"))
    )
    (net (code "69") (name "Net-(H1-Pad15)") (class "Default")
      (node (ref "H1") (pin "15") (pinfunction "15_15") (pintype "passive"))
      (node (ref "R26") (pin "2") (pinfunction "2_2") (pintype "passive"))
    )
    (net (code "70") (name "unconnected-(B2-NC-Pad3)") (class "Default")
      (node (ref "B2") (pin "3") (pinfunction "NC_3") (pintype "passive+no_connect"))
    )
    (net (code "71") (name "unconnected-(B3-NC-Pad3)") (class "Default")
      (node (ref "B3") (pin "3") (pinfunction "NC_3") (pintype "passive+no_connect"))
    )
    (net (code "72") (name "unconnected-(B4-NC-Pad3)") (class "Default")
      (node (ref "B4") (pin "3") (pinfunction "NC_3") (pintype "passive+no_connect"))
    )
    (net (code "73") (name "unconnected-(B5-NC-Pad3)") (class "Default")
      (node (ref "B5") (pin "3") (pinfunction "NC_3") (pintype "passive+no_connect"))
    )
    (net (code "74") (name "unconnected-(B7-NC_1-Pad4)") (class "Default")
      (node (ref "B7") (pin "4") (pinfunction "NC_1_4") (pintype "passive+no_connect"))
    )
    (net (code "75") (name "unconnected-(B7-NC_2-Pad5)") (class "Default")
      (node (ref "B7") (pin "5") (pinfunction "NC_2_5") (pintype "passive+no_connect"))
    )
    (net (code "76") (name "unconnected-(B8-NC_1-Pad4)") (class "Default")
      (node (ref "B8") (pin "4") (pinfunction "NC_1_4") (pintype "passive+no_connect"))
    )
    (net (code "77") (name "unconnected-(B8-NC_2-Pad5)") (class "Default")
      (node (ref "B8") (pin "5") (pinfunction "NC_2_5") (pintype "passive+no_connect"))
    )
    (net (code "78") (name "unconnected-(B9-NC_1-Pad4)") (class "Default")
      (node (ref "B9") (pin "4") (pinfunction "NC_1_4") (pintype "passive+no_connect"))
    )
    (net (code "79") (name "unconnected-(B9-NC_2-Pad5)") (class "Default")
      (node (ref "B9") (pin "5") (pinfunction "NC_2_5") (pintype "passive+no_connect"))
    )
    (net (code "80") (name "unconnected-(B10-NC_1-Pad4)") (class "Default")
      (node (ref "B10") (pin "4") (pinfunction "NC_1_4") (pintype "passive+no_connect"))
    )
    (net (code "81") (name "unconnected-(B10-NC_2-Pad5)") (class "Default")
      (node (ref "B10") (pin "5") (pinfunction "NC_2_5") (pintype "passive+no_connect"))
    )
  )
)
